# 08_User_IO.net
KiCad netlist of a schematic drawn in Altium Designer
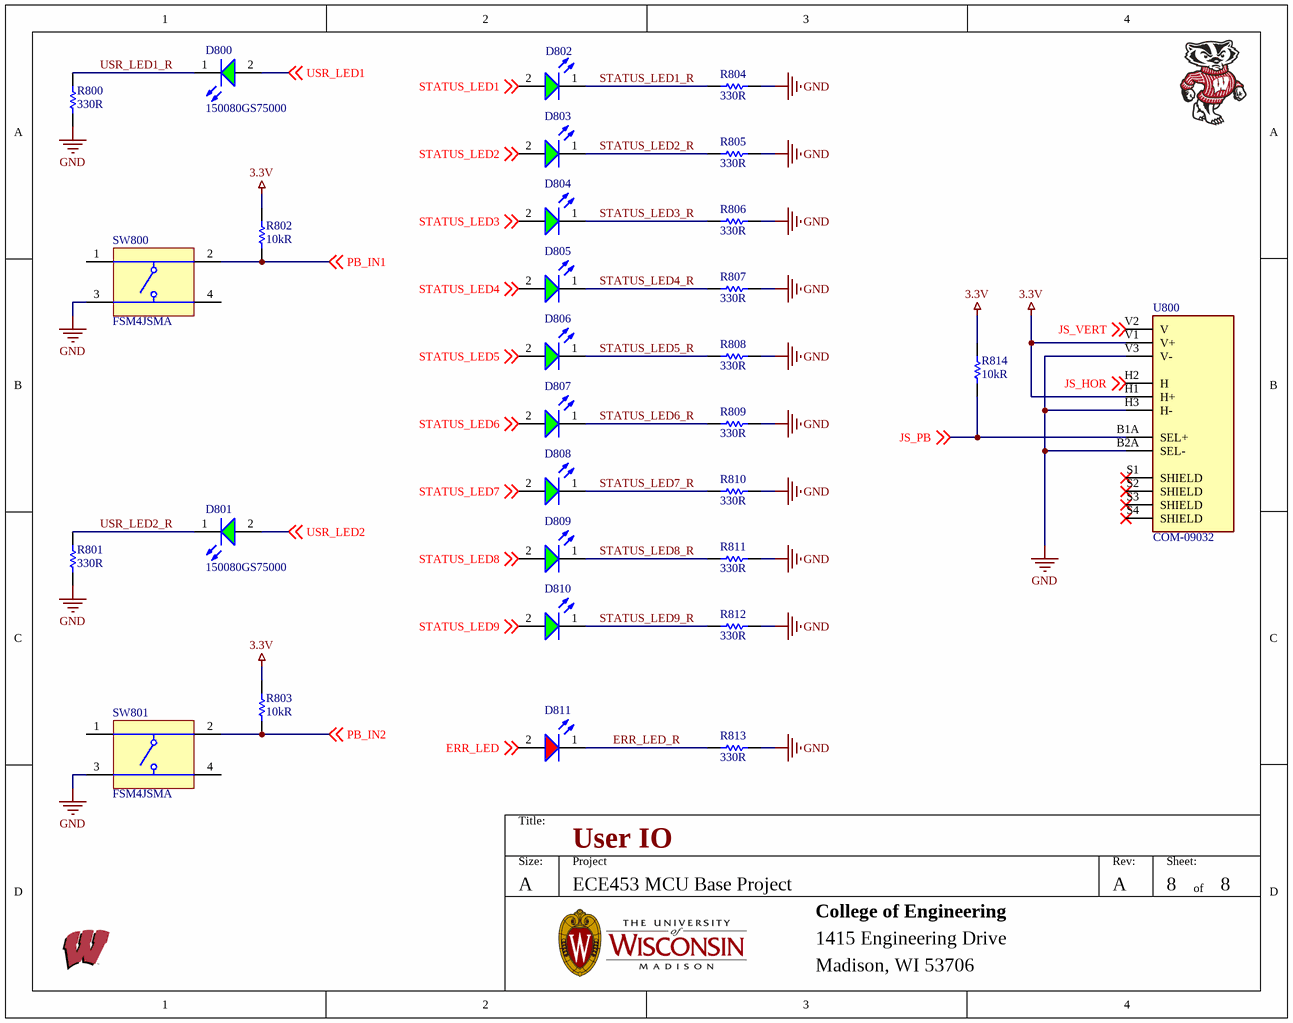
[diagram p0: 08_User_IO.SchDoc]

(export (version "E")
  (design (tool "Eeschema 10.0.6"))
  (components
    (comp (ref "D800")
      (value "150080GS75000")
      (footprint "WL-SMCW_0805_150080xx75000")
      (libsource (lib "Altium Content Vault") (part "LED_Green_2A-1K"))
    )
    (comp (ref "D801")
      (value "150080GS75000")
      (footprint "WL-SMCW_0805_150080xx75000")
      (libsource (lib "Altium Content Vault") (part "LED_Green_2A-1K"))
    )
    (comp (ref "D802")
      (value "~")
      (footprint "WL-SMCW_0805_150080xx75000")
      (libsource (lib "Altium Content Vault") (part "LED_Green_2A-1K"))
    )
    (comp (ref "D803")
      (value "~")
      (footprint "WL-SMCW_0805_150080xx75000")
      (libsource (lib "Altium Content Vault") (part "LED_Green_2A-1K"))
    )
    (comp (ref "D804")
      (value "~")
      (footprint "WL-SMCW_0805_150080xx75000")
      (libsource (lib "Altium Content Vault") (part "LED_Green_2A-1K"))
    )
    (comp (ref "D805")
      (value "~")
      (footprint "WL-SMCW_0805_150080xx75000")
      (libsource (lib "Altium Content Vault") (part "LED_Green_2A-1K"))
    )
    (comp (ref "D806")
      (value "~")
      (footprint "WL-SMCW_0805_150080xx75000")
      (libsource (lib "Altium Content Vault") (part "LED_Green_2A-1K"))
    )
    (comp (ref "D807")
      (value "~")
      (footprint "WL-SMCW_0805_150080xx75000")
      (libsource (lib "Altium Content Vault") (part "LED_Green_2A-1K"))
    )
    (comp (ref "D808")
      (value "~")
      (footprint "WL-SMCW_0805_150080xx75000")
      (libsource (lib "Altium Content Vault") (part "LED_Green_2A-1K"))
    )
    (comp (ref "D809")
      (value "~")
      (footprint "WL-SMCW_0805_150080xx75000")
      (libsource (lib "Altium Content Vault") (part "LED_Green_2A-1K"))
    )
    (comp (ref "D810")
      (value "~")
      (footprint "WL-SMCW_0805_150080xx75000")
      (libsource (lib "Altium Content Vault") (part "LED_Green_2A-1K"))
    )
    (comp (ref "D811")
      (value "~")
      (footprint "WL-SMCW_0805_150080xx75000")
      (libsource (lib "Altium Content Vault") (part "LED_Red_2A-1K"))
    )
    (comp (ref "R800")
      (value "330R")
      (footprint "RESC2013X60X40LL20T25")
      (fields (field (name "MANUFACTURER") "Panasonic") (field (name "PART NUMBER") "ERA6AEB331V"))
      (libsource (lib "Altium Content Vault") (part "RES"))
    )
    (comp (ref "R801")
      (value "330R")
      (footprint "RESC2013X60X40LL20T25")
      (fields (field (name "MANUFACTURER") "Panasonic") (field (name "PART NUMBER") "ERA6AEB331V"))
      (libsource (lib "Altium Content Vault") (part "RES"))
    )
    (comp (ref "R802")
      (value "10kR")
      (footprint "RESC2013X70X40ML20T20")
      (fields (field (name "MANUFACTURER") "Panasonic") (field (name "PART NUMBER") "ERJ-6ENF1002V"))
      (libsource (lib "Altium Content Vault") (part "RES"))
    )
    (comp (ref "R803")
      (value "10kR")
      (footprint "RESC2013X70X40ML20T20")
      (fields (field (name "MANUFACTURER") "Panasonic") (field (name "PART NUMBER") "ERJ-6ENF1002V"))
      (libsource (lib "Altium Content Vault") (part "RES"))
    )
    (comp (ref "R804")
      (value "330R")
      (footprint "RESC2013X60X40LL20T25")
      (fields (field (name "MANUFACTURER") "Panasonic") (field (name "PART NUMBER") "ERA6AEB331V"))
      (libsource (lib "Altium Content Vault") (part "RES"))
    )
    (comp (ref "R805")
      (value "330R")
      (footprint "RESC2013X60X40LL20T25")
      (fields (field (name "MANUFACTURER") "Panasonic") (field (name "PART NUMBER") "ERA6AEB331V"))
      (libsource (lib "Altium Content Vault") (part "RES"))
    )
    (comp (ref "R806")
      (value "330R")
      (footprint "RESC2013X60X40LL20T25")
      (fields (field (name "MANUFACTURER") "Panasonic") (field (name "PART NUMBER") "ERA6AEB331V"))
      (libsource (lib "Altium Content Vault") (part "RES"))
    )
    (comp (ref "R807")
      (value "330R")
      (footprint "RESC2013X60X40LL20T25")
      (fields (field (name "MANUFACTURER") "Panasonic") (field (name "PART NUMBER") "ERA6AEB331V"))
      (libsource (lib "Altium Content Vault") (part "RES"))
    )
    (comp (ref "R808")
      (value "330R")
      (footprint "RESC2013X60X40LL20T25")
      (fields (field (name "MANUFACTURER") "Panasonic") (field (name "PART NUMBER") "ERA6AEB331V"))
      (libsource (lib "Altium Content Vault") (part "RES"))
    )
    (comp (ref "R809")
      (value "330R")
      (footprint "RESC2013X60X40LL20T25")
      (fields (field (name "MANUFACTURER") "Panasonic") (field (name "PART NUMBER") "ERA6AEB331V"))
      (libsource (lib "Altium Content Vault") (part "RES"))
    )
    (comp (ref "R810")
      (value "330R")
      (footprint "RESC2013X60X40LL20T25")
      (fields (field (name "MANUFACTURER") "Panasonic") (field (name "PART NUMBER") "ERA6AEB331V"))
      (libsource (lib "Altium Content Vault") (part "RES"))
    )
    (comp (ref "R811")
      (value "330R")
      (footprint "RESC2013X60X40LL20T25")
      (fields (field (name "MANUFACTURER") "Panasonic") (field (name "PART NUMBER") "ERA6AEB331V"))
      (libsource (lib "Altium Content Vault") (part "RES"))
    )
    (comp (ref "R812")
      (value "330R")
      (footprint "RESC2013X60X40LL20T25")
      (fields (field (name "MANUFACTURER") "Panasonic") (field (name "PART NUMBER") "ERA6AEB331V"))
      (libsource (lib "Altium Content Vault") (part "RES"))
    )
    (comp (ref "R813")
      (value "330R")
      (footprint "RESC2013X60X40LL20T25")
      (fields (field (name "MANUFACTURER") "Panasonic") (field (name "PART NUMBER") "ERA6AEB331V"))
      (libsource (lib "Altium Content Vault") (part "RES"))
    )
    (comp (ref "R814")
      (value "10kR")
      (footprint "RESC2013X70X40ML20T20")
      (fields (field (name "MANUFACTURER") "Panasonic") (field (name "PART NUMBER") "ERJ-6ENF1002V"))
      (libsource (lib "Altium Content Vault") (part "RES"))
    )
    (comp (ref "SW800")
      (value "FSM4JSMA")
      (footprint "TECO-FSM4JSMA_V")
      (description "Swicth, SPST, 24 V, -35 to 85 degC, 4-Pin SMD, RoHS, Tape and Reel")
      (fields (field (name "MANUFACTURER") "TE Connectivity"))
      (libsource (lib "Altium Content Vault") (part "SW-SPST-4_A"))
    )
    (comp (ref "SW801")
      (value "FSM4JSMA")
      (footprint "TECO-FSM4JSMA_V")
      (description "Swicth, SPST, 24 V, -35 to 85 degC, 4-Pin SMD, RoHS, Tape and Reel")
      (fields (field (name "MANUFACTURER") "TE Connectivity"))
      (libsource (lib "Altium Content Vault") (part "SW-SPST-4_A"))
    )
    (comp (ref "U800")
      (value "COM-09032")
      (footprint "XDCR_COM-09032:XDCR_COM-09032")
      (description "Thumb Joystick")
      (libsource (lib "COM-09032") (part "COM-09032"))
    )
  )
  (nets
    (net (code "1") (name "/ERR_LED_R") (class "Default")
      (node (ref "D811") (pin "1") (pinfunction "K_1") (pintype "passive"))
      (node (ref "R813") (pin "1") (pinfunction "1_1") (pintype "passive"))
    )
    (net (code "2") (name "/STATUS_LED1_R") (class "Default")
      (node (ref "D802") (pin "1") (pinfunction "K_1") (pintype "passive"))
      (node (ref "R804") (pin "1") (pinfunction "1_1") (pintype "passive"))
    )
    (net (code "3") (name "/STATUS_LED2_R") (class "Default")
      (node (ref "D803") (pin "1") (pinfunction "K_1") (pintype "passive"))
      (node (ref "R805") (pin "1") (pinfunction "1_1") (pintype "passive"))
    )
    (net (code "4") (name "/STATUS_LED3_R") (class "Default")
      (node (ref "D804") (pin "1") (pinfunction "K_1") (pintype "passive"))
      (node (ref "R806") (pin "1") (pinfunction "1_1") (pintype "passive"))
    )
    (net (code "5") (name "/STATUS_LED4_R") (class "Default")
      (node (ref "D805") (pin "1") (pinfunction "K_1") (pintype "passive"))
      (node (ref "R807") (pin "1") (pinfunction "1_1") (pintype "passive"))
    )
    (net (code "6") (name "/STATUS_LED5_R") (class "Default")
      (node (ref "D806") (pin "1") (pinfunction "K_1") (pintype "passive"))
      (node (ref "R808") (pin "1") (pinfunction "1_1") (pintype "passive"))
    )
    (net (code "7") (name "/STATUS_LED6_R") (class "Default")
      (node (ref "D807") (pin "1") (pinfunction "K_1") (pintype "passive"))
      (node (ref "R809") (pin "1") (pinfunction "1_1") (pintype "passive"))
    )
    (net (code "8") (name "/STATUS_LED7_R") (class "Default")
      (node (ref "D808") (pin "1") (pinfunction "K_1") (pintype "passive"))
      (node (ref "R810") (pin "1") (pinfunction "1_1") (pintype "passive"))
    )
    (net (code "9") (name "/STATUS_LED8_R") (class "Default")
      (node (ref "D809") (pin "1") (pinfunction "K_1") (pintype "passive"))
      (node (ref "R811") (pin "1") (pinfunction "1_1") (pintype "passive"))
    )
    (net (code "10") (name "/STATUS_LED9_R") (class "Default")
      (node (ref "D810") (pin "1") (pinfunction "K_1") (pintype "passive"))
      (node (ref "R812") (pin "1") (pinfunction "1_1") (pintype "passive"))
    )
    (net (code "11") (name "/USR_LED1_R") (class "Default")
      (node (ref "D800") (pin "1") (pinfunction "K_1") (pintype "passive"))
      (node (ref "R800") (pin "1") (pinfunction "1_1") (pintype "passive"))
    )
    (net (code "12") (name "/USR_LED2_R") (class "Default")
      (node (ref "D801") (pin "1") (pinfunction "K_1") (pintype "passive"))
      (node (ref "R801") (pin "1") (pinfunction "1_1") (pintype "passive"))
    )
    (net (code "13") (name "3.3V") (class "Default")
      (node (ref "R802") (pin "2") (pinfunction "2_2") (pintype "passive"))
      (node (ref "R803") (pin "2") (pinfunction "2_2") (pintype "passive"))
      (node (ref "R814") (pin "2") (pinfunction "2_2") (pintype "passive"))
      (node (ref "U800") (pin "H1") (pinfunction "H+_H1") (pintype "passive"))
      (node (ref "U800") (pin "V1") (pinfunction "V+_V1") (pintype "passive"))
    )
    (net (code "14") (name "ERR_LED") (class "Default")
      (node (ref "D811") (pin "2") (pinfunction "A_2") (pintype "passive"))
    )
    (net (code "15") (name "GND") (class "Default")
      (node (ref "R800") (pin "2") (pinfunction "2_2") (pintype "passive"))
      (node (ref "R801") (pin "2") (pinfunction "2_2") (pintype "passive"))
      (node (ref "R804") (pin "2") (pinfunction "2_2") (pintype "passive"))
      (node (ref "R805") (pin "2") (pinfunction "2_2") (pintype "passive"))
      (node (ref "R806") (pin "2") (pinfunction "2_2") (pintype "passive"))
      (node (ref "R807") (pin "2") (pinfunction "2_2") (pintype "passive"))
      (node (ref "R808") (pin "2") (pinfunction "2_2") (pintype "passive"))
      (node (ref "R809") (pin "2") (pinfunction "2_2") (pintype "passive"))
      (node (ref "R810") (pin "2") (pinfunction "2_2") (pintype "passive"))
      (node (ref "R811") (pin "2") (pinfunction "2_2") (pintype "passive"))
      (node (ref "R812") (pin "2") (pinfunction "2_2") (pintype "passive"))
      (node (ref "R813") (pin "2") (pinfunction "2_2") (pintype "passive"))
      (node (ref "SW800") (pin "3") (pinfunction "3_3") (pintype "passive"))
      (node (ref "SW801") (pin "3") (pinfunction "3_3") (pintype "passive"))
      (node (ref "U800") (pin "B2A") (pinfunction "SEL-_B2A") (pintype "passive"))
      (node (ref "U800") (pin "H3") (pinfunction "H-_H3") (pintype "passive"))
      (node (ref "U800") (pin "V3") (pinfunction "V-_V3") (pintype "passive"))
    )
    (net (code "16") (name "JS_HOR") (class "Default")
      (node (ref "U800") (pin "H2") (pinfunction "H_H2") (pintype "passive"))
    )
    (net (code "17") (name "JS_PB") (class "Default")
      (node (ref "R814") (pin "1") (pinfunction "1_1") (pintype "passive"))
      (node (ref "U800") (pin "B1A") (pinfunction "SEL+_B1A") (pintype "passive"))
    )
    (net (code "18") (name "JS_VERT") (class "Default")
      (node (ref "U800") (pin "V2") (pinfunction "V_V2") (pintype "passive"))
    )
    (net (code "19") (name "PB_IN1") (class "Default")
      (node (ref "R802") (pin "1") (pinfunction "1_1") (pintype "passive"))
      (node (ref "SW800") (pin "2") (pinfunction "2_2") (pintype "passive"))
    )
    (net (code "20") (name "PB_IN2") (class "Default")
      (node (ref "R803") (pin "1") (pinfunction "1_1") (pintype "passive"))
      (node (ref "SW801") (pin "2") (pinfunction "2_2") (pintype "passive"))
    )
    (net (code "21") (name "STATUS_LED1") (class "Default")
      (node (ref "D802") (pin "2") (pinfunction "A_2") (pintype "passive"))
    )
    (net (code "22") (name "STATUS_LED2") (class "Default")
      (node (ref "D803") (pin "2") (pinfunction "A_2") (pintype "passive"))
    )
    (net (code "23") (name "STATUS_LED3") (class "Default")
      (node (ref "D804") (pin "2") (pinfunction "A_2") (pintype "passive"))
    )
    (net (code "24") (name "STATUS_LED4") (class "Default")
      (node (ref "D805") (pin "2") (pinfunction "A_2") (pintype "passive"))
    )
    (net (code "25") (name "STATUS_LED5") (class "Default")
      (node (ref "D806") (pin "2") (pinfunction "A_2") (pintype "passive"))
    )
    (net (code "26") (name "STATUS_LED6") (class "Default")
      (node (ref "D807") (pin "2") (pinfunction "A_2") (pintype "passive"))
    )
    (net (code "27") (name "STATUS_LED7") (class "Default")
      (node (ref "D808") (pin "2") (pinfunction "A_2") (pintype "passive"))
    )
    (net (code "28") (name "STATUS_LED8") (class "Default")
      (node (ref "D809") (pin "2") (pinfunction "A_2") (pintype "passive"))
    )
    (net (code "29") (name "STATUS_LED9") (class "Default")
      (node (ref "D810") (pin "2") (pinfunction "A_2") (pintype "passive"))
    )
    (net (code "30") (name "USR_LED1") (class "Default")
      (node (ref "D800") (pin "2") (pinfunction "A_2") (pintype "passive"))
    )
    (net (code "31") (name "USR_LED2") (class "Default")
      (node (ref "D801") (pin "2") (pinfunction "A_2") (pintype "passive"))
    )
    (net (code "32") (name "unconnected-(SW800-Pad1)") (class "Default")
      (node (ref "SW800") (pin "1") (pinfunction "1_1") (pintype "passive"))
    )
    (net (code "33") (name "unconnected-(SW800-Pad4)") (class "Default")
      (node (ref "SW800") (pin "4") (pinfunction "4_4") (pintype "passive"))
    )
    (net (code "34") (name "unconnected-(SW801-Pad1)") (class "Default")
      (node (ref "SW801") (pin "1") (pinfunction "1_1") (pintype "passive"))
    )
    (net (code "35") (name "unconnected-(SW801-Pad4)") (class "Default")
      (node (ref "SW801") (pin "4") (pinfunction "4_4") (pintype "passive"))
    )
    (net (code "36") (name "unconnected-(U800-SHIELD-PadS1)") (class "Default")
      (node (ref "U800") (pin "S1") (pinfunction "SHIELD_S1") (pintype "passive+no_connect"))
    )
    (net (code "37") (name "unconnected-(U800-SHIELD-PadS2)") (class "Default")
      (node (ref "U800") (pin "S2") (pinfunction "SHIELD_S2") (pintype "passive+no_connect"))
    )
    (net (code "38") (name "unconnected-(U800-SHIELD-PadS3)") (class "Default")
      (node (ref "U800") (pin "S3") (pinfunction "SHIELD_S3") (pintype "passive+no_connect"))
    )
    (net (code "39") (name "unconnected-(U800-SHIELD-PadS4)") (class "Default")
      (node (ref "U800") (pin "S4") (pinfunction "SHIELD_S4") (pintype "passive+no_connect"))
    )
  )
)
